# lab1-schematic.net
KiCad netlist of a schematic drawn in EAGLE
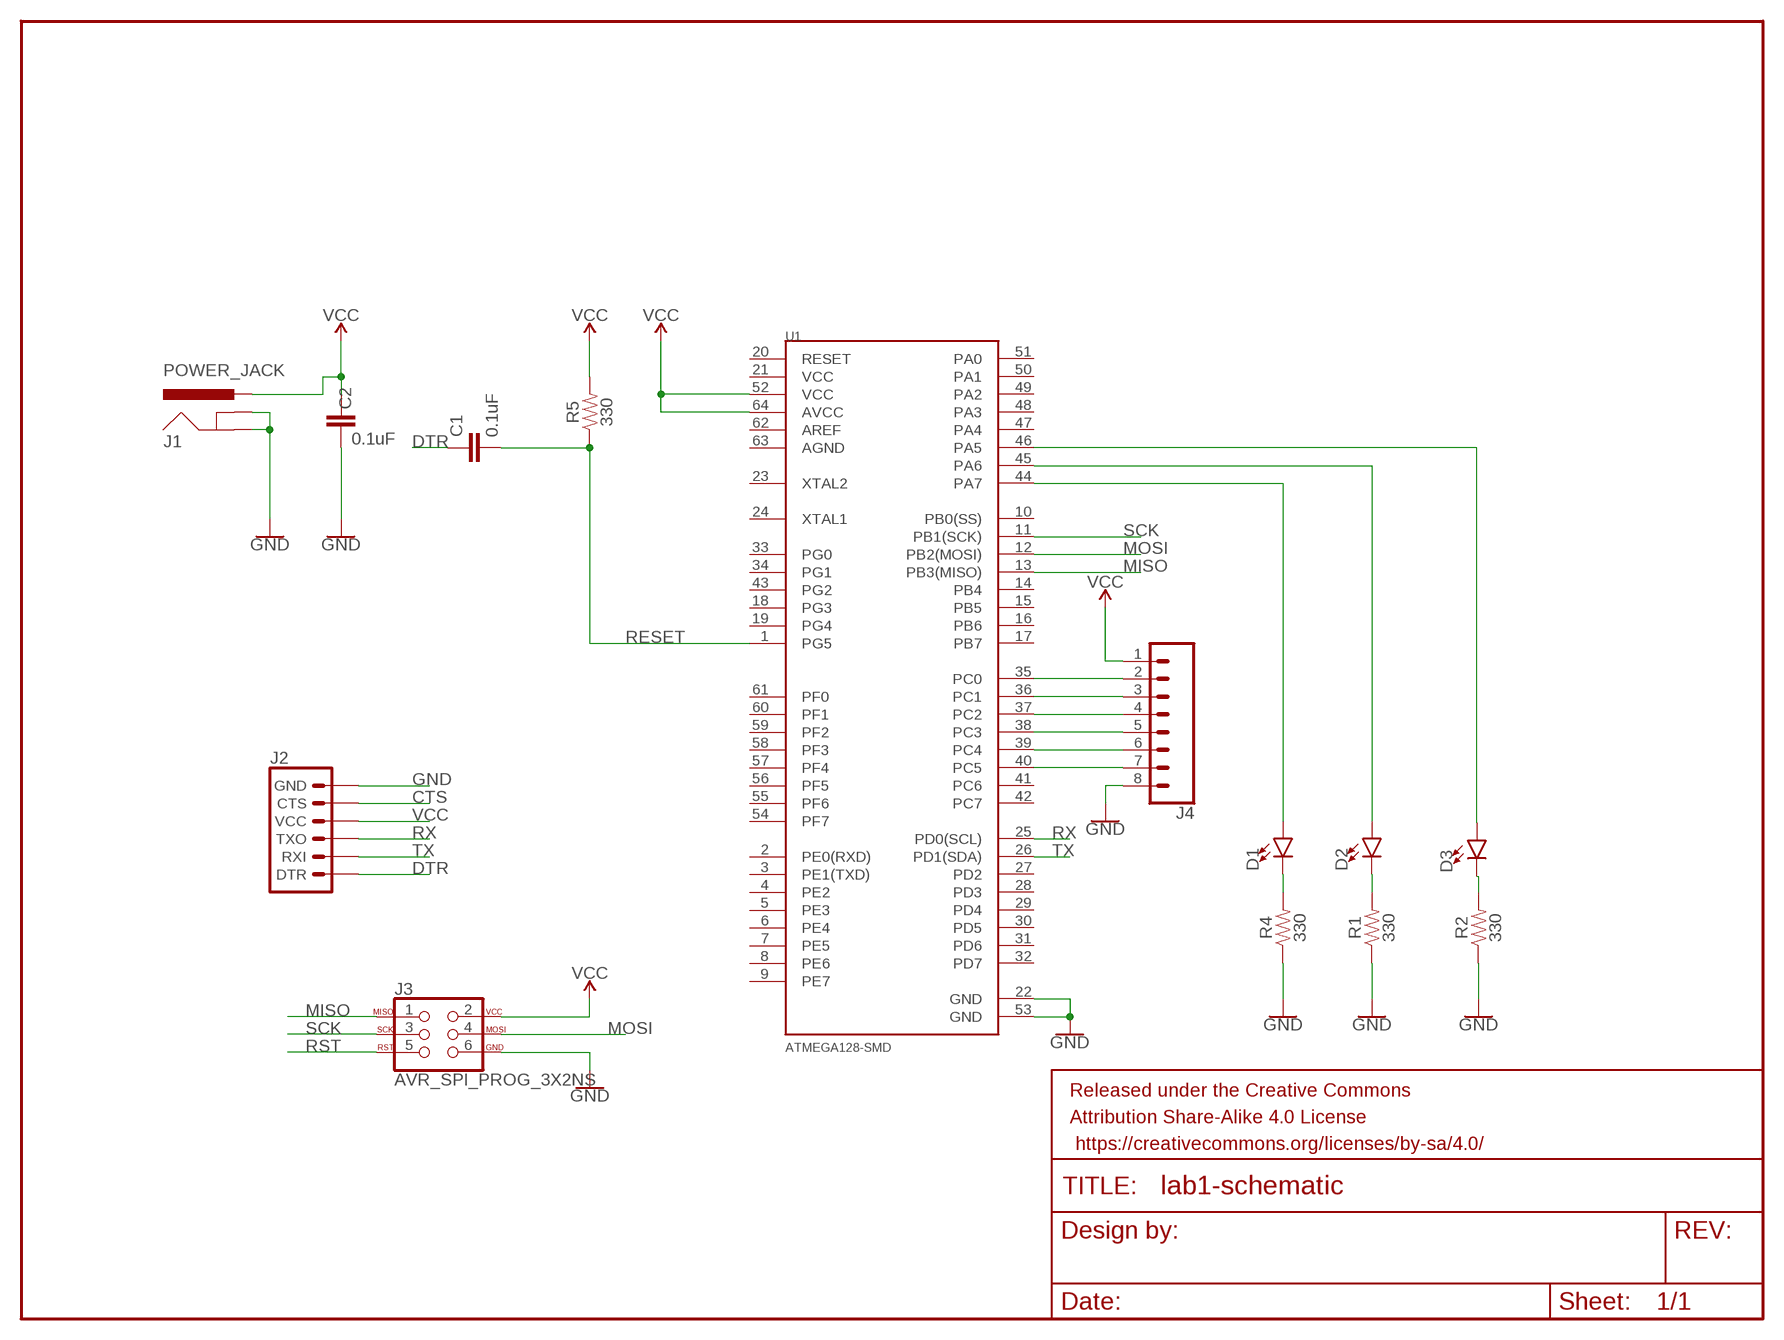
[diagram p0: schematic, sheet 1]

(export (version "E")
  (design (tool "Eeschema 10.0.6"))
  (components
    (comp (ref "C1")
      (value "0.1uF")
      (footprint "eagle-import:CAP-PTH-SMALL-KIT")
      (libsource (lib "eagle-import") (part "0.1UF-KIT-EZ-50V-20%"))
    )
    (comp (ref "C2")
      (value "0.1uF")
      (footprint "eagle-import:CAP-PTH-SMALL-KIT")
      (libsource (lib "eagle-import") (part "0.1UF-KIT-EZ-50V-20%"))
    )
    (comp (ref "D1")
      (value "LED3MM")
      (footprint "eagle-import:LED_3MM")
      (libsource (lib "eagle-import") (part "LED3MM"))
    )
    (comp (ref "D2")
      (value "LED3MM")
      (footprint "eagle-import:LED_3MM")
      (libsource (lib "eagle-import") (part "LED3MM"))
    )
    (comp (ref "D3")
      (value "LED3MM")
      (footprint "eagle-import:LED_3MM")
      (libsource (lib "eagle-import") (part "LED3MM"))
    )
    (comp (ref "FRAME1")
      (value "FRAME-LETTER")
      (footprint "eagle-import:CREATIVE_COMMONS")
      (libsource (lib "eagle-import") (part "FRAME-LETTER"))
    )
    (comp (ref "J1")
      (value "POWER_JACK")
      (footprint "eagle-import:POWER_JACK_PTH")
      (libsource (lib "eagle-import") (part "POWER_JACK"))
    )
    (comp (ref "J2")
      (value "6_PIN_SERIAL_TARGET")
      (footprint "eagle-import:1X06")
      (libsource (lib "eagle-import") (part "6_PIN_SERIAL_TARGET"))
    )
    (comp (ref "J3")
      (value "AVR_SPI_PROG_3X2NS")
      (footprint "eagle-import:2X3-NS")
      (libsource (lib "eagle-import") (part "AVR_SPI_PROG_3X2NS"))
    )
    (comp (ref "J4")
      (value "CONN_08\"")
      (footprint "eagle-import:1X08")
      (libsource (lib "eagle-import") (part "CONN_08{dblquote}"))
    )
    (comp (ref "R1")
      (value "330")
      (footprint "eagle-import:AXIAL-0.3")
      (libsource (lib "eagle-import") (part "330OHM-HORIZ-1/10W-5%"))
    )
    (comp (ref "R2")
      (value "330")
      (footprint "eagle-import:AXIAL-0.3")
      (libsource (lib "eagle-import") (part "330OHM-HORIZ-1/10W-5%"))
    )
    (comp (ref "R4")
      (value "330")
      (footprint "eagle-import:AXIAL-0.3")
      (libsource (lib "eagle-import") (part "330OHM-HORIZ-1/10W-5%"))
    )
    (comp (ref "R5")
      (value "330")
      (footprint "eagle-import:AXIAL-0.3")
      (libsource (lib "eagle-import") (part "330OHM-HORIZ-1/10W-5%"))
    )
    (comp (ref "U1")
      (value "ATMEGA128-SMD")
      (footprint "eagle-import:TQFP64_14X14MM")
      (libsource (lib "eagle-import") (part "ATMEGA128-SMD"))
    )
  )
  (nets
    (net (code "1") (name "/CTS") (class "Default")
      (node (ref "J2") (pin "5") (pinfunction "CTS_5") (pintype "passive"))
    )
    (net (code "2") (name "/DTR") (class "Default")
      (node (ref "C1") (pin "1") (pinfunction "1_1") (pintype "passive"))
      (node (ref "J2") (pin "1") (pinfunction "DTR_1") (pintype "passive"))
    )
    (net (code "3") (name "/MISO") (class "Default")
      (node (ref "J3") (pin "1") (pinfunction "1_1") (pintype "passive"))
      (node (ref "U1") (pin "13") (pinfunction "PB3(MISO)_13") (pintype "bidirectional"))
    )
    (net (code "4") (name "/MOSI") (class "Default")
      (node (ref "J3") (pin "4") (pinfunction "4_4") (pintype "passive"))
      (node (ref "U1") (pin "12") (pinfunction "PB2(MOSI)_12") (pintype "bidirectional"))
    )
    (net (code "5") (name "/RESET") (class "Default")
      (node (ref "C1") (pin "2") (pinfunction "2_2") (pintype "passive"))
      (node (ref "R5") (pin "P$1") (pinfunction "1_P$1") (pintype "passive"))
      (node (ref "U1") (pin "1") (pinfunction "PG5_1") (pintype "bidirectional"))
    )
    (net (code "6") (name "/RST") (class "Default")
      (node (ref "J3") (pin "5") (pinfunction "5_5") (pintype "passive"))
    )
    (net (code "7") (name "/RX") (class "Default")
      (node (ref "J2") (pin "3") (pinfunction "TXO_3") (pintype "passive"))
      (node (ref "U1") (pin "25") (pinfunction "PD0(SCL)_25") (pintype "bidirectional"))
    )
    (net (code "8") (name "/SCK") (class "Default")
      (node (ref "J3") (pin "3") (pinfunction "3_3") (pintype "passive"))
      (node (ref "U1") (pin "11") (pinfunction "PB1(SCK)_11") (pintype "bidirectional"))
    )
    (net (code "9") (name "/TX") (class "Default")
      (node (ref "J2") (pin "2") (pinfunction "RXI_2") (pintype "passive"))
      (node (ref "U1") (pin "26") (pinfunction "PD1(SDA)_26") (pintype "bidirectional"))
    )
    (net (code "10") (name "GND") (class "Default")
      (node (ref "C2") (pin "2") (pinfunction "2_2") (pintype "passive"))
      (node (ref "J1") (pin "GND") (pinfunction "GND_GND") (pintype "bidirectional"))
      (node (ref "J1") (pin "GNDBREAK") (pinfunction "GNDBREAK_GNDBREAK") (pintype "bidirectional"))
      (node (ref "J2") (pin "6") (pinfunction "GND_6") (pintype "passive"))
      (node (ref "J3") (pin "6") (pinfunction "6_6") (pintype "passive"))
      (node (ref "J4") (pin "8") (pinfunction "8_8") (pintype "passive"))
      (node (ref "R1") (pin "P$1") (pinfunction "1_P$1") (pintype "passive"))
      (node (ref "R2") (pin "P$1") (pinfunction "1_P$1") (pintype "passive"))
      (node (ref "R4") (pin "P$1") (pinfunction "1_P$1") (pintype "passive"))
      (node (ref "U1") (pin "22") (pinfunction "GND_22") (pintype "bidirectional"))
      (node (ref "U1") (pin "53") (pinfunction "GND_53") (pintype "bidirectional"))
    )
    (net (code "11") (name "Net-(D1-C)") (class "Default")
      (node (ref "D1") (pin "K") (pinfunction "C_K") (pintype "passive"))
      (node (ref "R4") (pin "P$2") (pinfunction "2_P$2") (pintype "passive"))
    )
    (net (code "12") (name "Net-(D2-C)") (class "Default")
      (node (ref "D2") (pin "K") (pinfunction "C_K") (pintype "passive"))
      (node (ref "R1") (pin "P$2") (pinfunction "2_P$2") (pintype "passive"))
    )
    (net (code "13") (name "Net-(D3-C)") (class "Default")
      (node (ref "D3") (pin "K") (pinfunction "C_K") (pintype "passive"))
      (node (ref "R2") (pin "P$2") (pinfunction "2_P$2") (pintype "passive"))
    )
    (net (code "14") (name "Net-(U1-PA5)") (class "Default")
      (node (ref "D3") (pin "A") (pinfunction "A_A") (pintype "passive"))
      (node (ref "U1") (pin "46") (pinfunction "PA5_46") (pintype "bidirectional"))
    )
    (net (code "15") (name "Net-(U1-PA6)") (class "Default")
      (node (ref "D2") (pin "A") (pinfunction "A_A") (pintype "passive"))
      (node (ref "U1") (pin "45") (pinfunction "PA6_45") (pintype "bidirectional"))
    )
    (net (code "16") (name "Net-(U1-PA7)") (class "Default")
      (node (ref "D1") (pin "A") (pinfunction "A_A") (pintype "passive"))
      (node (ref "U1") (pin "44") (pinfunction "PA7_44") (pintype "bidirectional"))
    )
    (net (code "17") (name "Net-(U1-PC0)") (class "Default")
      (node (ref "J4") (pin "2") (pinfunction "2_2") (pintype "passive"))
      (node (ref "U1") (pin "35") (pinfunction "PC0_35") (pintype "bidirectional"))
    )
    (net (code "18") (name "Net-(U1-PC1)") (class "Default")
      (node (ref "J4") (pin "3") (pinfunction "3_3") (pintype "passive"))
      (node (ref "U1") (pin "36") (pinfunction "PC1_36") (pintype "bidirectional"))
    )
    (net (code "19") (name "Net-(U1-PC2)") (class "Default")
      (node (ref "J4") (pin "4") (pinfunction "4_4") (pintype "passive"))
      (node (ref "U1") (pin "37") (pinfunction "PC2_37") (pintype "bidirectional"))
    )
    (net (code "20") (name "Net-(U1-PC3)") (class "Default")
      (node (ref "J4") (pin "5") (pinfunction "5_5") (pintype "passive"))
      (node (ref "U1") (pin "38") (pinfunction "PC3_38") (pintype "bidirectional"))
    )
    (net (code "21") (name "Net-(U1-PC4)") (class "Default")
      (node (ref "J4") (pin "6") (pinfunction "6_6") (pintype "passive"))
      (node (ref "U1") (pin "39") (pinfunction "PC4_39") (pintype "bidirectional"))
    )
    (net (code "22") (name "Net-(U1-PC5)") (class "Default")
      (node (ref "J4") (pin "7") (pinfunction "7_7") (pintype "passive"))
      (node (ref "U1") (pin "40") (pinfunction "PC5_40") (pintype "bidirectional"))
    )
    (net (code "23") (name "VCC") (class "Default")
      (node (ref "C2") (pin "1") (pinfunction "1_1") (pintype "passive"))
      (node (ref "J1") (pin "PWR") (pinfunction "PWR_PWR") (pintype "bidirectional"))
      (node (ref "J2") (pin "4") (pinfunction "VCC_4") (pintype "passive"))
      (node (ref "J3") (pin "2") (pinfunction "2_2") (pintype "passive"))
      (node (ref "J4") (pin "1") (pinfunction "1_1") (pintype "passive"))
      (node (ref "R5") (pin "P$2") (pinfunction "2_P$2") (pintype "passive"))
      (node (ref "U1") (pin "52") (pinfunction "VCC_52") (pintype "bidirectional"))
      (node (ref "U1") (pin "64") (pinfunction "AVCC_64") (pintype "bidirectional"))
    )
    (net (code "24") (name "unconnected-(U1-AGND-Pad63)") (class "Default")
      (node (ref "U1") (pin "63") (pinfunction "AGND_63") (pintype "bidirectional"))
    )
    (net (code "25") (name "unconnected-(U1-AREF-Pad62)") (class "Default")
      (node (ref "U1") (pin "62") (pinfunction "AREF_62") (pintype "bidirectional"))
    )
    (net (code "26") (name "unconnected-(U1-PA0-Pad51)") (class "Default")
      (node (ref "U1") (pin "51") (pinfunction "PA0_51") (pintype "bidirectional"))
    )
    (net (code "27") (name "unconnected-(U1-PA1-Pad50)") (class "Default")
      (node (ref "U1") (pin "50") (pinfunction "PA1_50") (pintype "bidirectional"))
    )
    (net (code "28") (name "unconnected-(U1-PA2-Pad49)") (class "Default")
      (node (ref "U1") (pin "49") (pinfunction "PA2_49") (pintype "bidirectional"))
    )
    (net (code "29") (name "unconnected-(U1-PA3-Pad48)") (class "Default")
      (node (ref "U1") (pin "48") (pinfunction "PA3_48") (pintype "bidirectional"))
    )
    (net (code "30") (name "unconnected-(U1-PA4-Pad47)") (class "Default")
      (node (ref "U1") (pin "47") (pinfunction "PA4_47") (pintype "bidirectional"))
    )
    (net (code "31") (name "unconnected-(U1-PB0(SS)-Pad10)") (class "Default")
      (node (ref "U1") (pin "10") (pinfunction "PB0(SS)_10") (pintype "bidirectional"))
    )
    (net (code "32") (name "unconnected-(U1-PB4-Pad14)") (class "Default")
      (node (ref "U1") (pin "14") (pinfunction "PB4_14") (pintype "bidirectional"))
    )
    (net (code "33") (name "unconnected-(U1-PB5-Pad15)") (class "Default")
      (node (ref "U1") (pin "15") (pinfunction "PB5_15") (pintype "bidirectional"))
    )
    (net (code "34") (name "unconnected-(U1-PB6-Pad16)") (class "Default")
      (node (ref "U1") (pin "16") (pinfunction "PB6_16") (pintype "bidirectional"))
    )
    (net (code "35") (name "unconnected-(U1-PB7-Pad17)") (class "Default")
      (node (ref "U1") (pin "17") (pinfunction "PB7_17") (pintype "bidirectional"))
    )
    (net (code "36") (name "unconnected-(U1-PC6-Pad41)") (class "Default")
      (node (ref "U1") (pin "41") (pinfunction "PC6_41") (pintype "bidirectional"))
    )
    (net (code "37") (name "unconnected-(U1-PC7-Pad42)") (class "Default")
      (node (ref "U1") (pin "42") (pinfunction "PC7_42") (pintype "bidirectional"))
    )
    (net (code "38") (name "unconnected-(U1-PD2-Pad27)") (class "Default")
      (node (ref "U1") (pin "27") (pinfunction "PD2_27") (pintype "bidirectional"))
    )
    (net (code "39") (name "unconnected-(U1-PD3-Pad28)") (class "Default")
      (node (ref "U1") (pin "28") (pinfunction "PD3_28") (pintype "bidirectional"))
    )
    (net (code "40") (name "unconnected-(U1-PD4-Pad29)") (class "Default")
      (node (ref "U1") (pin "29") (pinfunction "PD4_29") (pintype "bidirectional"))
    )
    (net (code "41") (name "unconnected-(U1-PD5-Pad30)") (class "Default")
      (node (ref "U1") (pin "30") (pinfunction "PD5_30") (pintype "bidirectional"))
    )
    (net (code "42") (name "unconnected-(U1-PD6-Pad31)") (class "Default")
      (node (ref "U1") (pin "31") (pinfunction "PD6_31") (pintype "bidirectional"))
    )
    (net (code "43") (name "unconnected-(U1-PD7-Pad32)") (class "Default")
      (node (ref "U1") (pin "32") (pinfunction "PD7_32") (pintype "bidirectional"))
    )
    (net (code "44") (name "unconnected-(U1-PE0(RXD)-Pad2)") (class "Default")
      (node (ref "U1") (pin "2") (pinfunction "PE0(RXD)_2") (pintype "bidirectional"))
    )
    (net (code "45") (name "unconnected-(U1-PE1(TXD)-Pad3)") (class "Default")
      (node (ref "U1") (pin "3") (pinfunction "PE1(TXD)_3") (pintype "bidirectional"))
    )
    (net (code "46") (name "unconnected-(U1-PE2-Pad4)") (class "Default")
      (node (ref "U1") (pin "4") (pinfunction "PE2_4") (pintype "bidirectional"))
    )
    (net (code "47") (name "unconnected-(U1-PE3-Pad5)") (class "Default")
      (node (ref "U1") (pin "5") (pinfunction "PE3_5") (pintype "bidirectional"))
    )
    (net (code "48") (name "unconnected-(U1-PE4-Pad6)") (class "Default")
      (node (ref "U1") (pin "6") (pinfunction "PE4_6") (pintype "bidirectional"))
    )
    (net (code "49") (name "unconnected-(U1-PE5-Pad7)") (class "Default")
      (node (ref "U1") (pin "7") (pinfunction "PE5_7") (pintype "bidirectional"))
    )
    (net (code "50") (name "unconnected-(U1-PE6-Pad8)") (class "Default")
      (node (ref "U1") (pin "8") (pinfunction "PE6_8") (pintype "bidirectional"))
    )
    (net (code "51") (name "unconnected-(U1-PE7-Pad9)") (class "Default")
      (node (ref "U1") (pin "9") (pinfunction "PE7_9") (pintype "bidirectional"))
    )
    (net (code "52") (name "unconnected-(U1-PF0-Pad61)") (class "Default")
      (node (ref "U1") (pin "61") (pinfunction "PF0_61") (pintype "bidirectional"))
    )
    (net (code "53") (name "unconnected-(U1-PF1-Pad60)") (class "Default")
      (node (ref "U1") (pin "60") (pinfunction "PF1_60") (pintype "bidirectional"))
    )
    (net (code "54") (name "unconnected-(U1-PF2-Pad59)") (class "Default")
      (node (ref "U1") (pin "59") (pinfunction "PF2_59") (pintype "bidirectional"))
    )
    (net (code "55") (name "unconnected-(U1-PF3-Pad58)") (class "Default")
      (node (ref "U1") (pin "58") (pinfunction "PF3_58") (pintype "bidirectional"))
    )
    (net (code "56") (name "unconnected-(U1-PF4-Pad57)") (class "Default")
      (node (ref "U1") (pin "57") (pinfunction "PF4_57") (pintype "bidirectional"))
    )
    (net (code "57") (name "unconnected-(U1-PF5-Pad56)") (class "Default")
      (node (ref "U1") (pin "56") (pinfunction "PF5_56") (pintype "bidirectional"))
    )
    (net (code "58") (name "unconnected-(U1-PF6-Pad55)") (class "Default")
      (node (ref "U1") (pin "55") (pinfunction "PF6_55") (pintype "bidirectional"))
    )
    (net (code "59") (name "unconnected-(U1-PF7-Pad54)") (class "Default")
      (node (ref "U1") (pin "54") (pinfunction "PF7_54") (pintype "bidirectional"))
    )
    (net (code "60") (name "unconnected-(U1-PG0-Pad33)") (class "Default")
      (node (ref "U1") (pin "33") (pinfunction "PG0_33") (pintype "bidirectional"))
    )
    (net (code "61") (name "unconnected-(U1-PG1-Pad34)") (class "Default")
      (node (ref "U1") (pin "34") (pinfunction "PG1_34") (pintype "bidirectional"))
    )
    (net (code "62") (name "unconnected-(U1-PG2-Pad43)") (class "Default")
      (node (ref "U1") (pin "43") (pinfunction "PG2_43") (pintype "bidirectional"))
    )
    (net (code "63") (name "unconnected-(U1-PG3-Pad18)") (class "Default")
      (node (ref "U1") (pin "18") (pinfunction "PG3_18") (pintype "bidirectional"))
    )
    (net (code "64") (name "unconnected-(U1-PG4-Pad19)") (class "Default")
      (node (ref "U1") (pin "19") (pinfunction "PG4_19") (pintype "bidirectional"))
    )
    (net (code "65") (name "unconnected-(U1-RESET-Pad20)") (class "Default")
      (node (ref "U1") (pin "20") (pinfunction "RESET_20") (pintype "bidirectional"))
    )
    (net (code "66") (name "unconnected-(U1-VCC-Pad21)") (class "Default")
      (node (ref "U1") (pin "21") (pinfunction "VCC_21") (pintype "bidirectional"))
    )
    (net (code "67") (name "unconnected-(U1-XTAL1-Pad24)") (class "Default")
      (node (ref "U1") (pin "24") (pinfunction "XTAL1_24") (pintype "bidirectional"))
    )
    (net (code "68") (name "unconnected-(U1-XTAL2-Pad23)") (class "Default")
      (node (ref "U1") (pin "23") (pinfunction "XTAL2_23") (pintype "bidirectional"))
    )
  )
)
